# flute.net
KiCad netlist of a schematic drawn in EAGLE
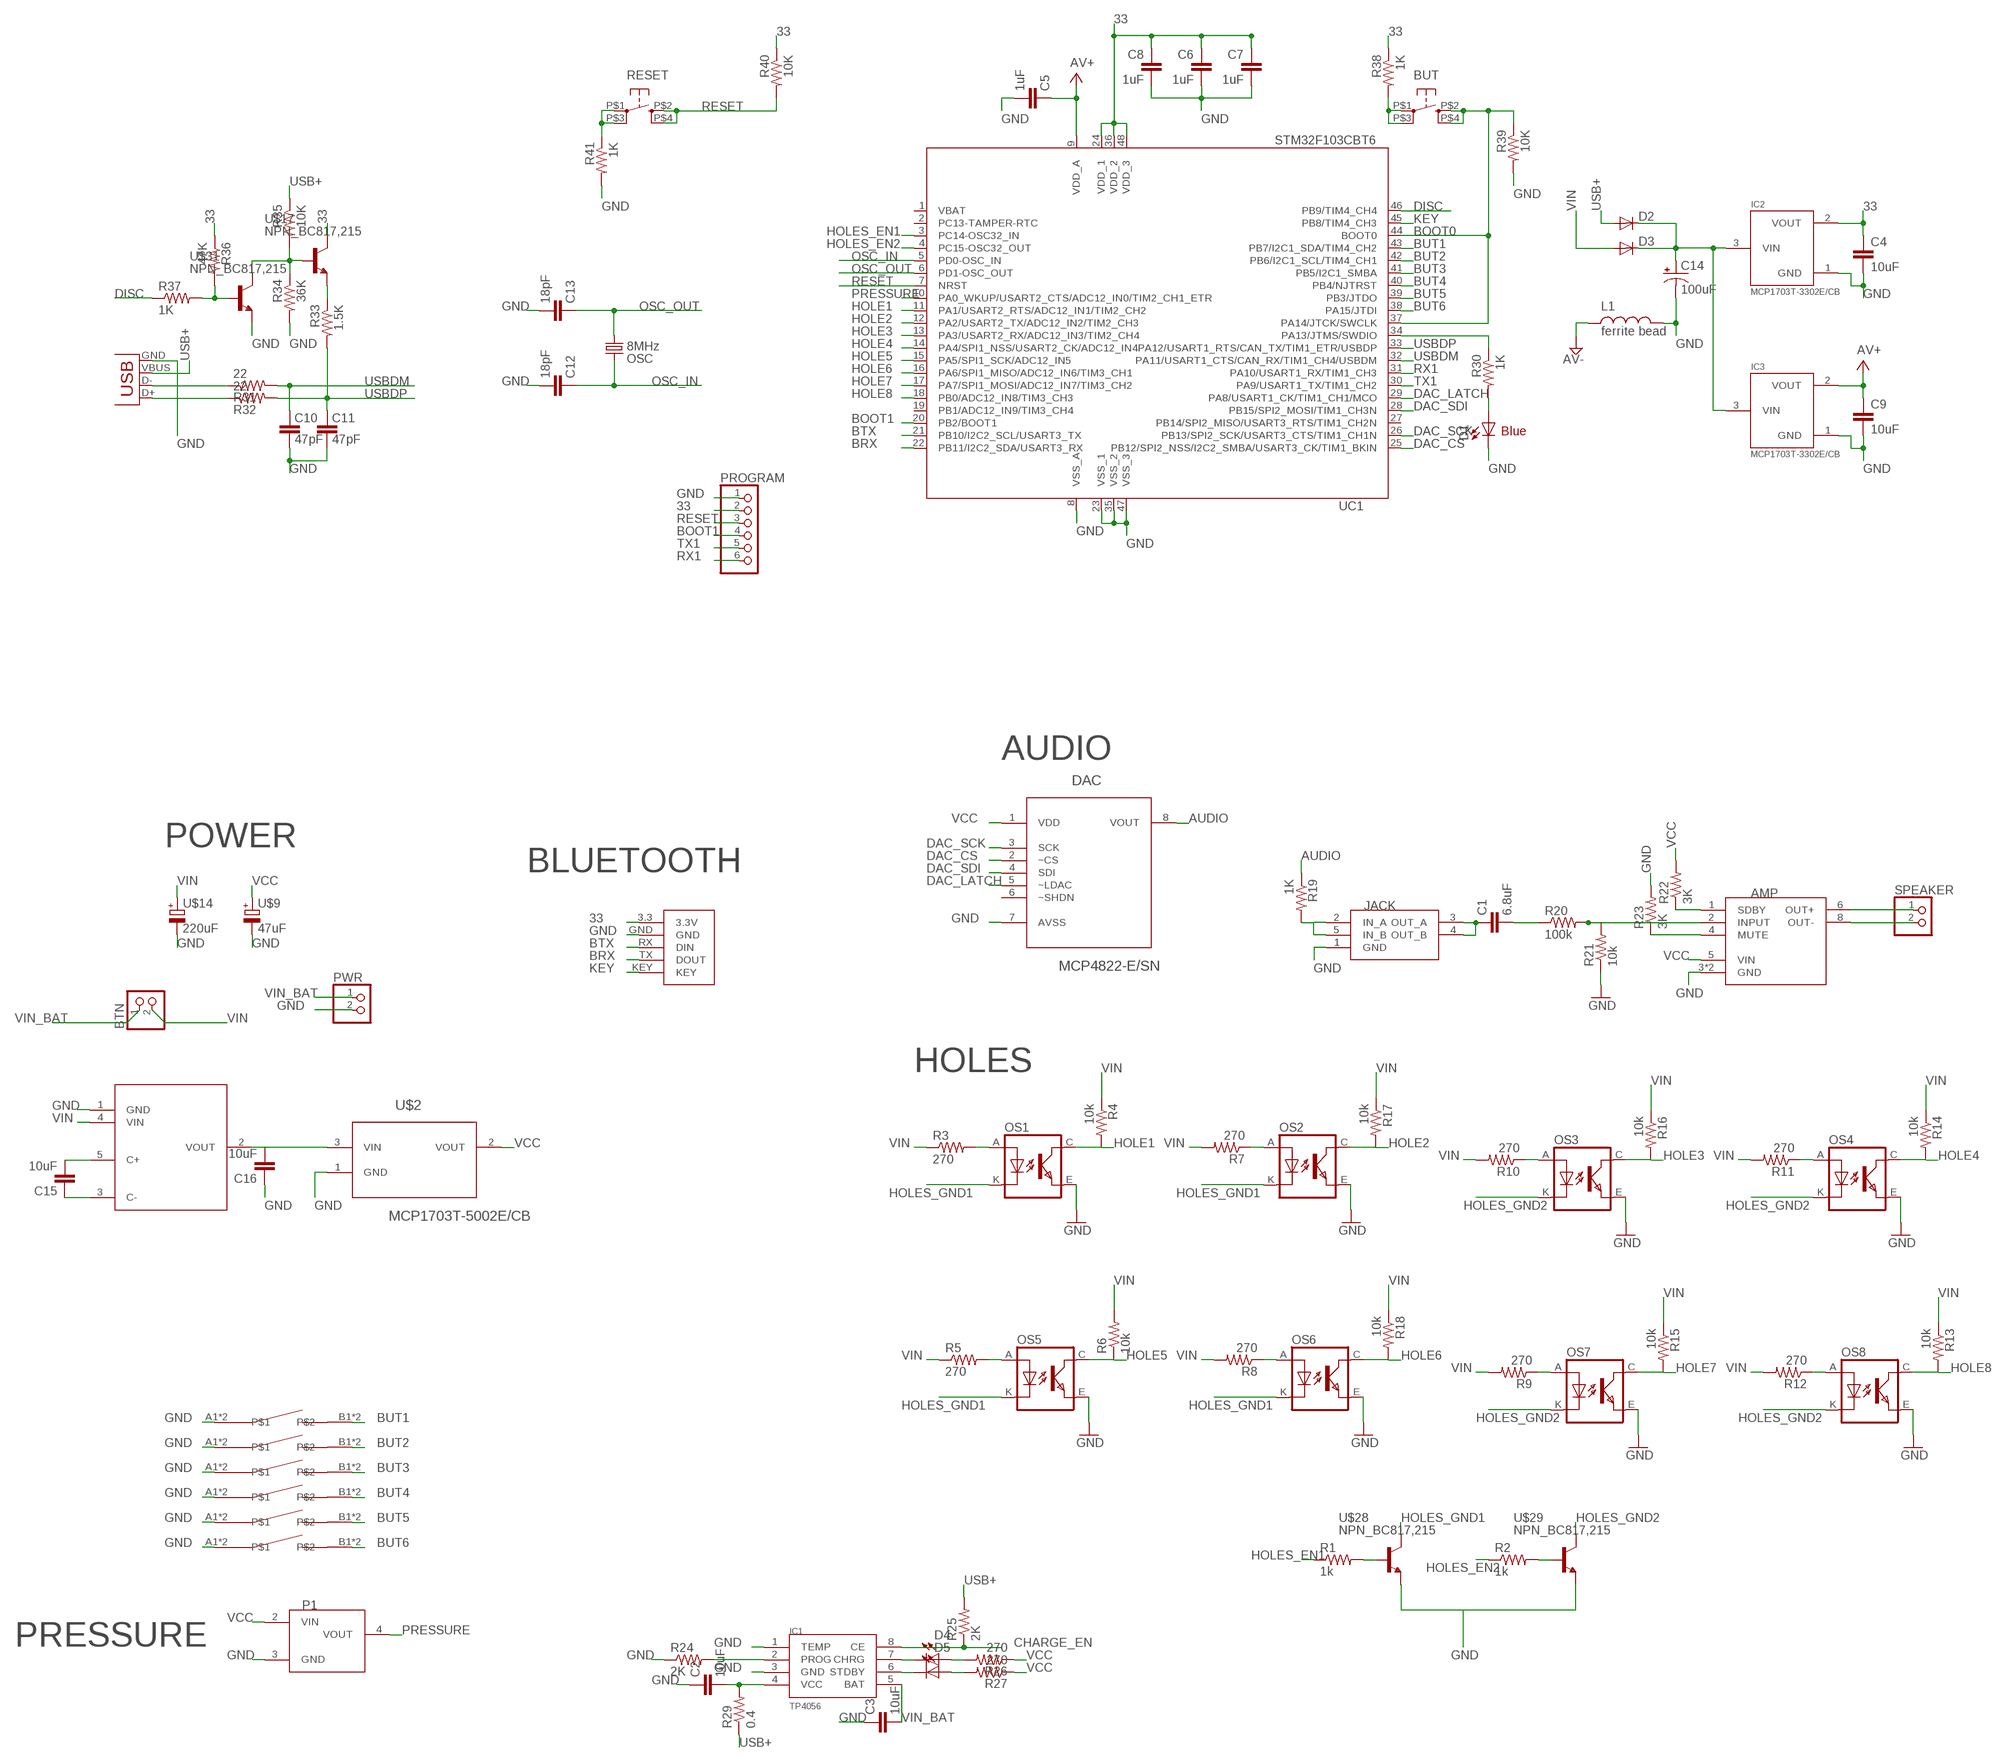
[diagram p0: schematic, sheet 1]

(export (version "E")
  (design (tool "Eeschema 10.0.6"))
  (components
    (comp (ref "AMP")
      (value "AN7511DIP8")
      (footprint "eagle-import:DIL08")
      (libsource (lib "eagle-import") (part "AN7511DIP8"))
    )
    (comp (ref "BTN")
      (value "CONNEC_1X02BASIC")
      (footprint "eagle-import:CONNEC_1X02")
      (libsource (lib "eagle-import") (part "CONNEC_1X02BASIC"))
    )
    (comp (ref "BUT")
      (value "KMR211GLFS")
      (footprint "eagle-import:PUSHBUTTON-KMR241GLFS")
      (libsource (lib "eagle-import") (part "BUTTON-KMR241GLFS"))
    )
    (comp (ref "C1")
      (value "6.8uF")
      (footprint "eagle-import:0805")
      (libsource (lib "eagle-import") (part "SparkFun-Passives_CAP0805"))
    )
    (comp (ref "C2")
      (value "10uF")
      (footprint "eagle-import:0805")
      (libsource (lib "eagle-import") (part "SparkFun-Passives_CAP0805"))
    )
    (comp (ref "C3")
      (value "10uF")
      (footprint "eagle-import:0805")
      (libsource (lib "eagle-import") (part "SparkFun-Passives_CAP0805"))
    )
    (comp (ref "C4")
      (value "10uF")
      (footprint "eagle-import:0805")
      (libsource (lib "eagle-import") (part "SparkFun2_CAP0805"))
    )
    (comp (ref "C5")
      (value "1uF")
      (footprint "eagle-import:C0402")
      (libsource (lib "eagle-import") (part "CAP0402"))
    )
    (comp (ref "C6")
      (value "1uF")
      (footprint "eagle-import:C0402")
      (libsource (lib "eagle-import") (part "CAP0402"))
    )
    (comp (ref "C7")
      (value "1uF")
      (footprint "eagle-import:C0402")
      (libsource (lib "eagle-import") (part "CAP0402"))
    )
    (comp (ref "C8")
      (value "1uF")
      (footprint "eagle-import:C0402")
      (libsource (lib "eagle-import") (part "CAP0402"))
    )
    (comp (ref "C9")
      (value "10uF")
      (footprint "eagle-import:0805")
      (libsource (lib "eagle-import") (part "SparkFun2_CAP0805"))
    )
    (comp (ref "C10")
      (value "47pF")
      (footprint "eagle-import:C0402")
      (libsource (lib "eagle-import") (part "CAP0402"))
    )
    (comp (ref "C11")
      (value "47pF")
      (footprint "eagle-import:C0402")
      (libsource (lib "eagle-import") (part "CAP0402"))
    )
    (comp (ref "C12")
      (value "18pF")
      (footprint "eagle-import:C0402")
      (libsource (lib "eagle-import") (part "CAP0402"))
    )
    (comp (ref "C13")
      (value "18pF")
      (footprint "eagle-import:C0402")
      (libsource (lib "eagle-import") (part "CAP0402"))
    )
    (comp (ref "C14")
      (value "100uF")
      (footprint "eagle-import:EIA3216")
      (libsource (lib "eagle-import") (part "CAP_POL1206"))
    )
    (comp (ref "C15")
      (value "10uF")
      (footprint "eagle-import:0805")
      (libsource (lib "eagle-import") (part "SparkFun-Passives_CAP0805"))
    )
    (comp (ref "C16")
      (value "10uF")
      (footprint "eagle-import:0805")
      (libsource (lib "eagle-import") (part "SparkFun-Passives_CAP0805"))
    )
    (comp (ref "D1")
      (value "Blue")
      (footprint "eagle-import:LED-1206")
      (libsource (lib "eagle-import") (part "LED1206"))
    )
    (comp (ref "D2")
      (value "DIODESOD")
      (footprint "eagle-import:SOD-323")
      (libsource (lib "eagle-import") (part "DIODESOD"))
    )
    (comp (ref "D3")
      (value "DIODESOD")
      (footprint "eagle-import:SOD-323")
      (libsource (lib "eagle-import") (part "DIODESOD"))
    )
    (comp (ref "D4")
      (value "Red")
      (footprint "eagle-import:LED-1206")
      (libsource (lib "eagle-import") (part "LED1206"))
    )
    (comp (ref "D5")
      (value "Green")
      (footprint "eagle-import:LED-1206")
      (libsource (lib "eagle-import") (part "LED1206"))
    )
    (comp (ref "DAC")
      (value "MCP4822-E/SN")
      (footprint "eagle-import:SOIC8-N_MC")
      (libsource (lib "eagle-import") (part "MCP4822-E/SN"))
    )
    (comp (ref "IC1")
      (value "TP4056")
      (footprint "eagle-import:SOP-8")
      (libsource (lib "eagle-import") (part "TP4056"))
    )
    (comp (ref "IC2")
      (value "MCP1703T-3302E/CB")
      (footprint "eagle-import:SOT23")
      (libsource (lib "eagle-import") (part "MCP1700T"))
    )
    (comp (ref "IC3")
      (value "MCP1703T-3302E/CB")
      (footprint "eagle-import:SOT23")
      (libsource (lib "eagle-import") (part "MCP1700T"))
    )
    (comp (ref "JACK")
      (value "JACK")
      (footprint "eagle-import:3F07")
      (libsource (lib "eagle-import") (part "JACK"))
    )
    (comp (ref "L1")
      (value "ferrite bead")
      (footprint "eagle-import:0603")
      (libsource (lib "eagle-import") (part "INDUCTOR0603"))
    )
    (comp (ref "OS1")
      (value "TCRT5000")
      (footprint "eagle-import:TCRT5000")
      (libsource (lib "eagle-import") (part "TCRT5000"))
    )
    (comp (ref "OS2")
      (value "TCRT5000")
      (footprint "eagle-import:TCRT5000")
      (libsource (lib "eagle-import") (part "TCRT5000"))
    )
    (comp (ref "OS3")
      (value "TCRT5000")
      (footprint "eagle-import:TCRT5000")
      (libsource (lib "eagle-import") (part "TCRT5000"))
    )
    (comp (ref "OS4")
      (value "TCRT5000")
      (footprint "eagle-import:TCRT5000")
      (libsource (lib "eagle-import") (part "TCRT5000"))
    )
    (comp (ref "OS5")
      (value "TCRT5000")
      (footprint "eagle-import:TCRT5000")
      (libsource (lib "eagle-import") (part "TCRT5000"))
    )
    (comp (ref "OS6")
      (value "TCRT5000")
      (footprint "eagle-import:TCRT5000")
      (libsource (lib "eagle-import") (part "TCRT5000"))
    )
    (comp (ref "OS7")
      (value "TCRT5000")
      (footprint "eagle-import:TCRT5000")
      (libsource (lib "eagle-import") (part "TCRT5000"))
    )
    (comp (ref "OS8")
      (value "TCRT5000")
      (footprint "eagle-import:TCRT5000")
      (libsource (lib "eagle-import") (part "TCRT5000"))
    )
    (comp (ref "OSC")
      (value "8MHz")
      (footprint "eagle-import:CRYSTAL-SMD-5X3")
      (libsource (lib "eagle-import") (part "CRYSTAL5X3"))
    )
    (comp (ref "P1")
      (value "PRESSURE_SENSOR")
      (footprint "eagle-import:MPXV5050GP")
      (libsource (lib "eagle-import") (part "PRESSURE_SENSOR"))
    )
    (comp (ref "PROGRAM")
      (value "CONNEC_1X066PADS")
      (footprint "eagle-import:6PADS")
      (libsource (lib "eagle-import") (part "CONNEC_1X066PADS"))
    )
    (comp (ref "PWR")
      (value "CONNEC_1X02BASIC")
      (footprint "eagle-import:CONNEC_1X02")
      (libsource (lib "eagle-import") (part "CONNEC_1X02BASIC"))
    )
    (comp (ref "R1")
      (value "1k")
      (footprint "eagle-import:0805")
      (libsource (lib "eagle-import") (part "RESISTOR0805-RES"))
    )
    (comp (ref "R2")
      (value "1k")
      (footprint "eagle-import:0805")
      (libsource (lib "eagle-import") (part "RESISTOR0805-RES"))
    )
    (comp (ref "R3")
      (value "270")
      (footprint "eagle-import:0805")
      (libsource (lib "eagle-import") (part "RESISTOR0805-RES"))
    )
    (comp (ref "R4")
      (value "10k")
      (footprint "eagle-import:0805")
      (libsource (lib "eagle-import") (part "RESISTOR0805-RES"))
    )
    (comp (ref "R5")
      (value "270")
      (footprint "eagle-import:0805")
      (libsource (lib "eagle-import") (part "RESISTOR0805-RES"))
    )
    (comp (ref "R6")
      (value "10k")
      (footprint "eagle-import:0805")
      (libsource (lib "eagle-import") (part "RESISTOR0805-RES"))
    )
    (comp (ref "R7")
      (value "270")
      (footprint "eagle-import:0805")
      (libsource (lib "eagle-import") (part "RESISTOR0805-RES"))
    )
    (comp (ref "R8")
      (value "270")
      (footprint "eagle-import:0805")
      (libsource (lib "eagle-import") (part "RESISTOR0805-RES"))
    )
    (comp (ref "R9")
      (value "270")
      (footprint "eagle-import:0805")
      (libsource (lib "eagle-import") (part "RESISTOR0805-RES"))
    )
    (comp (ref "R10")
      (value "270")
      (footprint "eagle-import:0805")
      (libsource (lib "eagle-import") (part "RESISTOR0805-RES"))
    )
    (comp (ref "R11")
      (value "270")
      (footprint "eagle-import:0805")
      (libsource (lib "eagle-import") (part "RESISTOR0805-RES"))
    )
    (comp (ref "R12")
      (value "270")
      (footprint "eagle-import:0805")
      (libsource (lib "eagle-import") (part "RESISTOR0805-RES"))
    )
    (comp (ref "R13")
      (value "10k")
      (footprint "eagle-import:0805")
      (libsource (lib "eagle-import") (part "RESISTOR0805-RES"))
    )
    (comp (ref "R14")
      (value "10k")
      (footprint "eagle-import:0805")
      (libsource (lib "eagle-import") (part "RESISTOR0805-RES"))
    )
    (comp (ref "R15")
      (value "10k")
      (footprint "eagle-import:0805")
      (libsource (lib "eagle-import") (part "RESISTOR0805-RES"))
    )
    (comp (ref "R16")
      (value "10k")
      (footprint "eagle-import:0805")
      (libsource (lib "eagle-import") (part "RESISTOR0805-RES"))
    )
    (comp (ref "R17")
      (value "10k")
      (footprint "eagle-import:0805")
      (libsource (lib "eagle-import") (part "RESISTOR0805-RES"))
    )
    (comp (ref "R18")
      (value "10k")
      (footprint "eagle-import:0805")
      (libsource (lib "eagle-import") (part "RESISTOR0805-RES"))
    )
    (comp (ref "R19")
      (value "1K")
      (footprint "eagle-import:0805")
      (libsource (lib "eagle-import") (part "RESISTOR0805-RES"))
    )
    (comp (ref "R20")
      (value "100k")
      (footprint "eagle-import:0805")
      (libsource (lib "eagle-import") (part "RESISTOR0805-RES"))
    )
    (comp (ref "R21")
      (value "10k")
      (footprint "eagle-import:0805")
      (libsource (lib "eagle-import") (part "RESISTOR0805-RES"))
    )
    (comp (ref "R22")
      (value "3K")
      (footprint "eagle-import:0805")
      (libsource (lib "eagle-import") (part "RESISTOR0805-RES"))
    )
    (comp (ref "R23")
      (value "3K")
      (footprint "eagle-import:0805")
      (libsource (lib "eagle-import") (part "RESISTOR0805-RES"))
    )
    (comp (ref "R24")
      (value "2K")
      (footprint "eagle-import:0805")
      (libsource (lib "eagle-import") (part "RESISTOR0805-RES"))
    )
    (comp (ref "R25")
      (value "2K")
      (footprint "eagle-import:0805")
      (libsource (lib "eagle-import") (part "RESISTOR0805-RES"))
    )
    (comp (ref "R26")
      (value "270")
      (footprint "eagle-import:0805")
      (libsource (lib "eagle-import") (part "RESISTOR0805-RES"))
    )
    (comp (ref "R27")
      (value "270")
      (footprint "eagle-import:0805")
      (libsource (lib "eagle-import") (part "RESISTOR0805-RES"))
    )
    (comp (ref "R29")
      (value "0.4")
      (footprint "eagle-import:0805")
      (libsource (lib "eagle-import") (part "RESISTOR0805-RES"))
    )
    (comp (ref "R30")
      (value "1K")
      (footprint "eagle-import:0805")
      (libsource (lib "eagle-import") (part "RESISTOR0805-RES"))
    )
    (comp (ref "R31")
      (value "22")
      (footprint "eagle-import:0805")
      (libsource (lib "eagle-import") (part "RESISTOR0805-RES"))
    )
    (comp (ref "R32")
      (value "22")
      (footprint "eagle-import:0805")
      (libsource (lib "eagle-import") (part "RESISTOR0805-RES"))
    )
    (comp (ref "R33")
      (value "1.5K")
      (footprint "eagle-import:0805")
      (libsource (lib "eagle-import") (part "RESISTOR0805-RES"))
    )
    (comp (ref "R34")
      (value "36K")
      (footprint "eagle-import:0805")
      (libsource (lib "eagle-import") (part "RESISTOR0805-RES"))
    )
    (comp (ref "R35")
      (value "10K")
      (footprint "eagle-import:0805")
      (libsource (lib "eagle-import") (part "RESISTOR0805-RES"))
    )
    (comp (ref "R36")
      (value "47K")
      (footprint "eagle-import:0805")
      (libsource (lib "eagle-import") (part "RESISTOR0805-RES"))
    )
    (comp (ref "R37")
      (value "1K")
      (footprint "eagle-import:0805")
      (libsource (lib "eagle-import") (part "RESISTOR0805-RES"))
    )
    (comp (ref "R38")
      (value "1K")
      (footprint "eagle-import:0805")
      (libsource (lib "eagle-import") (part "RESISTOR0805-RES"))
    )
    (comp (ref "R39")
      (value "10K")
      (footprint "eagle-import:0805")
      (libsource (lib "eagle-import") (part "RESISTOR0805-RES"))
    )
    (comp (ref "R40")
      (value "10K")
      (footprint "eagle-import:0805")
      (libsource (lib "eagle-import") (part "RESISTOR0805-RES"))
    )
    (comp (ref "R41")
      (value "1K")
      (footprint "eagle-import:0805")
      (libsource (lib "eagle-import") (part "RESISTOR0805-RES"))
    )
    (comp (ref "RESET")
      (value "KMR211GLFS")
      (footprint "eagle-import:PUSHBUTTON-KMR241GLFS")
      (libsource (lib "eagle-import") (part "BUTTON-KMR241GLFS"))
    )
    (comp (ref "SPEAKER")
      (value "CONNEC_1X02BASIC")
      (footprint "eagle-import:CONNEC_1X02")
      (libsource (lib "eagle-import") (part "CONNEC_1X02BASIC"))
    )
    (comp (ref "U$1")
      (value "MAX1683")
      (footprint "eagle-import:SOT23-5")
      (libsource (lib "eagle-import") (part "MAX1683"))
    )
    (comp (ref "U$2")
      (value "MCP1703T-5002E/CB")
      (footprint "eagle-import:SOT95P300X145-3N")
      (libsource (lib "eagle-import") (part "MCP1703T-5002E/CB"))
    )
    (comp (ref "U$9")
      (value "47uF")
      (footprint "eagle-import:PANASONIC_D")
      (libsource (lib "eagle-import") (part "CPOL_EUPANASONIC_D"))
    )
    (comp (ref "U$14")
      (value "220uF")
      (footprint "eagle-import:PANASONIC_D8")
      (libsource (lib "eagle-import") (part "CPOL_EUPANASONIC_D8"))
    )
    (comp (ref "U$17")
      (value "NPN_BC817,215")
      (footprint "eagle-import:SOT-23")
      (libsource (lib "eagle-import") (part "NPN_BC817,215"))
    )
    (comp (ref "U$18")
      (value "SWITCH6X6X10")
      (footprint "eagle-import:SWITCH_6X6X10")
      (libsource (lib "eagle-import") (part "SWITCH6X6X10"))
    )
    (comp (ref "U$19")
      (value "SWITCH6X6X10")
      (footprint "eagle-import:SWITCH_6X6X10")
      (libsource (lib "eagle-import") (part "SWITCH6X6X10"))
    )
    (comp (ref "U$20")
      (value "SWITCH6X6X10")
      (footprint "eagle-import:SWITCH_6X6X10")
      (libsource (lib "eagle-import") (part "SWITCH6X6X10"))
    )
    (comp (ref "U$21")
      (value "SWITCH6X6X10")
      (footprint "eagle-import:SWITCH_6X6X10")
      (libsource (lib "eagle-import") (part "SWITCH6X6X10"))
    )
    (comp (ref "U$22")
      (value "SWITCH6X6X10")
      (footprint "eagle-import:SWITCH_6X6X10")
      (libsource (lib "eagle-import") (part "SWITCH6X6X10"))
    )
    (comp (ref "U$23")
      (value "SWITCH6X6X10")
      (footprint "eagle-import:SWITCH_6X6X10")
      (libsource (lib "eagle-import") (part "SWITCH6X6X10"))
    )
    (comp (ref "U$24")
      (value "HC05")
      (footprint "eagle-import:HC-05")
      (libsource (lib "eagle-import") (part "HC05"))
    )
    (comp (ref "U$28")
      (value "NPN_BC817,215")
      (footprint "eagle-import:SOT-23")
      (libsource (lib "eagle-import") (part "NPN_BC817,215"))
    )
    (comp (ref "U$29")
      (value "NPN_BC817,215")
      (footprint "eagle-import:SOT-23")
      (libsource (lib "eagle-import") (part "NPN_BC817,215"))
    )
    (comp (ref "U$31")
      (value "NPN_BC817,215")
      (footprint "eagle-import:SOT-23")
      (libsource (lib "eagle-import") (part "NPN_BC817,215"))
    )
    (comp (ref "UC1")
      (value "STM32F103CBT6")
      (footprint "eagle-import:LQFP48")
      (libsource (lib "eagle-import") (part "STM32F103CB"))
    )
    (comp (ref "X1")
      (value "USB-MINIB")
      (footprint "eagle-import:USB-MINIB")
      (libsource (lib "eagle-import") (part "USBSMD"))
    )
  )
  (nets
    (net (code "1") (name "/33") (class "Default")
      (node (ref "C4") (pin "1") (pinfunction "1_1") (pintype "passive"))
      (node (ref "C6") (pin "1") (pinfunction "1_1") (pintype "passive"))
      (node (ref "C7") (pin "1") (pinfunction "1_1") (pintype "passive"))
      (node (ref "C8") (pin "1") (pinfunction "1_1") (pintype "passive"))
      (node (ref "IC2") (pin "2") (pinfunction "VOUT_2") (pintype "bidirectional"))
      (node (ref "PROGRAM") (pin "2") (pinfunction "2_2") (pintype "passive"))
      (node (ref "R36") (pin "1") (pinfunction "1_1") (pintype "passive"))
      (node (ref "R38") (pin "1") (pinfunction "1_1") (pintype "passive"))
      (node (ref "R40") (pin "1") (pinfunction "1_1") (pintype "passive"))
      (node (ref "U$17") (pin "3") (pinfunction "C_3") (pintype "passive"))
      (node (ref "U$24") (pin "3.3") (pinfunction "3.3V_3.3") (pintype "bidirectional"))
      (node (ref "UC1") (pin "24") (pinfunction "VDD_1_24") (pintype "power_in"))
      (node (ref "UC1") (pin "36") (pinfunction "VDD_2_36") (pintype "power_in"))
      (node (ref "UC1") (pin "48") (pinfunction "VDD_3_48") (pintype "power_in"))
    )
    (net (code "2") (name "/AUDIO") (class "Default")
      (node (ref "DAC") (pin "8") (pinfunction "VOUT_8") (pintype "output"))
      (node (ref "R19") (pin "1") (pinfunction "1_1") (pintype "passive"))
    )
    (net (code "3") (name "/BOOT1") (class "Default")
      (node (ref "PROGRAM") (pin "4") (pinfunction "4_4") (pintype "passive"))
      (node (ref "UC1") (pin "20") (pinfunction "PB2/BOOT1_20") (pintype "bidirectional"))
    )
    (net (code "4") (name "/BRX") (class "Default")
      (node (ref "U$24") (pin "TX") (pinfunction "DOUT_TX") (pintype "bidirectional"))
      (node (ref "UC1") (pin "22") (pinfunction "PB11/I2C2_SDA/USART3_RX_22") (pintype "input"))
    )
    (net (code "5") (name "/BTX") (class "Default")
      (node (ref "U$24") (pin "RX") (pinfunction "DIN_RX") (pintype "bidirectional"))
      (node (ref "UC1") (pin "21") (pinfunction "PB10/I2C2_SCL/USART3_TX_21") (pintype "input"))
    )
    (net (code "6") (name "/BUT1") (class "Default")
      (node (ref "U$18") (pin "B1") (pinfunction "P$2_B1") (pintype "bidirectional"))
      (node (ref "U$18") (pin "B2") (pinfunction "P$2_B2") (pintype "bidirectional"))
      (node (ref "UC1") (pin "43") (pinfunction "PB7/I2C1_SDA/TIM4_CH2_43") (pintype "bidirectional"))
    )
    (net (code "7") (name "/BUT2") (class "Default")
      (node (ref "U$19") (pin "B1") (pinfunction "P$2_B1") (pintype "bidirectional"))
      (node (ref "U$19") (pin "B2") (pinfunction "P$2_B2") (pintype "bidirectional"))
      (node (ref "UC1") (pin "42") (pinfunction "PB6/I2C1_SCL/TIM4_CH1_42") (pintype "input"))
    )
    (net (code "8") (name "/BUT3") (class "Default")
      (node (ref "U$20") (pin "B1") (pinfunction "P$2_B1") (pintype "bidirectional"))
      (node (ref "U$20") (pin "B2") (pinfunction "P$2_B2") (pintype "bidirectional"))
      (node (ref "UC1") (pin "41") (pinfunction "PB5/I2C1_SMBA_41") (pintype "input"))
    )
    (net (code "9") (name "/BUT4") (class "Default")
      (node (ref "U$21") (pin "B1") (pinfunction "P$2_B1") (pintype "bidirectional"))
      (node (ref "U$21") (pin "B2") (pinfunction "P$2_B2") (pintype "bidirectional"))
      (node (ref "UC1") (pin "40") (pinfunction "PB4/NJTRST_40") (pintype "bidirectional"))
    )
    (net (code "10") (name "/BUT5") (class "Default")
      (node (ref "U$22") (pin "B1") (pinfunction "P$2_B1") (pintype "bidirectional"))
      (node (ref "U$22") (pin "B2") (pinfunction "P$2_B2") (pintype "bidirectional"))
      (node (ref "UC1") (pin "39") (pinfunction "PB3/JTDO_39") (pintype "bidirectional"))
    )
    (net (code "11") (name "/BUT6") (class "Default")
      (node (ref "U$23") (pin "B1") (pinfunction "P$2_B1") (pintype "bidirectional"))
      (node (ref "U$23") (pin "B2") (pinfunction "P$2_B2") (pintype "bidirectional"))
      (node (ref "UC1") (pin "38") (pinfunction "PA15/JTDI_38") (pintype "bidirectional"))
    )
    (net (code "12") (name "/CHARGE_EN") (class "Default")
      (node (ref "IC1") (pin "8") (pinfunction "CE_8") (pintype "bidirectional"))
      (node (ref "R25") (pin "1") (pinfunction "1_1") (pintype "passive"))
    )
    (net (code "13") (name "/DAC_CS") (class "Default")
      (node (ref "DAC") (pin "2") (pinfunction "~{CS}_2") (pintype "input"))
      (node (ref "UC1") (pin "25") (pinfunction "PB12/SPI2_NSS/I2C2_SMBA/USART3_CK/TIM1_BKIN_25") (pintype "input"))
    )
    (net (code "14") (name "/DAC_LATCH") (class "Default")
      (node (ref "DAC") (pin "5") (pinfunction "~{LDAC}_5") (pintype "input"))
      (node (ref "UC1") (pin "29") (pinfunction "PA8/USART1_CK/TIM1_CH1/MCO_29") (pintype "bidirectional"))
    )
    (net (code "15") (name "/DAC_SCK") (class "Default")
      (node (ref "DAC") (pin "3") (pinfunction "SCK_3") (pintype "input"))
      (node (ref "UC1") (pin "26") (pinfunction "PB13/SPI2_SCK/USART3_CTS/TIM1_CH1N_26") (pintype "input"))
    )
    (net (code "16") (name "/DAC_SDI") (class "Default")
      (node (ref "DAC") (pin "4") (pinfunction "SDI_4") (pintype "input"))
      (node (ref "UC1") (pin "28") (pinfunction "PB15/SPI2_MOSI/TIM1_CH3N_28") (pintype "input"))
    )
    (net (code "17") (name "/DISC") (class "Default")
      (node (ref "R37") (pin "1") (pinfunction "1_1") (pintype "passive"))
      (node (ref "UC1") (pin "46") (pinfunction "PB9/TIM4_CH4_46") (pintype "input"))
    )
    (net (code "18") (name "/HOLE1") (class "Default")
      (node (ref "OS1") (pin "C") (pinfunction "COLLECTOR_C") (pintype "passive"))
      (node (ref "R4") (pin "2") (pinfunction "2_2") (pintype "passive"))
      (node (ref "UC1") (pin "11") (pinfunction "PA1/USART2_RTS/ADC12_IN1/TIM2_CH2_11") (pintype "bidirectional"))
    )
    (net (code "19") (name "/HOLE2") (class "Default")
      (node (ref "OS2") (pin "C") (pinfunction "COLLECTOR_C") (pintype "passive"))
      (node (ref "R17") (pin "2") (pinfunction "2_2") (pintype "passive"))
      (node (ref "UC1") (pin "12") (pinfunction "PA2/USART2_TX/ADC12_IN2/TIM2_CH3_12") (pintype "bidirectional"))
    )
    (net (code "20") (name "/HOLE3") (class "Default")
      (node (ref "OS3") (pin "C") (pinfunction "COLLECTOR_C") (pintype "passive"))
      (node (ref "R16") (pin "2") (pinfunction "2_2") (pintype "passive"))
      (node (ref "UC1") (pin "13") (pinfunction "PA3/USART2_RX/ADC12_IN3/TIM2_CH4_13") (pintype "bidirectional"))
    )
    (net (code "21") (name "/HOLE4") (class "Default")
      (node (ref "OS4") (pin "C") (pinfunction "COLLECTOR_C") (pintype "passive"))
      (node (ref "R14") (pin "2") (pinfunction "2_2") (pintype "passive"))
      (node (ref "UC1") (pin "14") (pinfunction "PA4/SPI1_NSS/USART2_CK/ADC12_IN4_14") (pintype "bidirectional"))
    )
    (net (code "22") (name "/HOLE5") (class "Default")
      (node (ref "OS5") (pin "C") (pinfunction "COLLECTOR_C") (pintype "passive"))
      (node (ref "R6") (pin "1") (pinfunction "1_1") (pintype "passive"))
      (node (ref "UC1") (pin "15") (pinfunction "PA5/SPI1_SCK/ADC12_IN5_15") (pintype "bidirectional"))
    )
    (net (code "23") (name "/HOLE6") (class "Default")
      (node (ref "OS6") (pin "C") (pinfunction "COLLECTOR_C") (pintype "passive"))
      (node (ref "R18") (pin "2") (pinfunction "2_2") (pintype "passive"))
      (node (ref "UC1") (pin "16") (pinfunction "PA6/SPI1_MISO/ADC12_IN6/TIM3_CH1_16") (pintype "bidirectional"))
    )
    (net (code "24") (name "/HOLE7") (class "Default")
      (node (ref "OS7") (pin "C") (pinfunction "COLLECTOR_C") (pintype "passive"))
      (node (ref "R15") (pin "2") (pinfunction "2_2") (pintype "passive"))
      (node (ref "UC1") (pin "17") (pinfunction "PA7/SPI1_MOSI/ADC12_IN7/TIM3_CH2_17") (pintype "bidirectional"))
    )
    (net (code "25") (name "/HOLE8") (class "Default")
      (node (ref "OS8") (pin "C") (pinfunction "COLLECTOR_C") (pintype "passive"))
      (node (ref "R13") (pin "2") (pinfunction "2_2") (pintype "passive"))
      (node (ref "UC1") (pin "18") (pinfunction "PB0/ADC12_IN8/TIM3_CH3_18") (pintype "bidirectional"))
    )
    (net (code "26") (name "/HOLES_EN1") (class "Default")
      (node (ref "R1") (pin "1") (pinfunction "1_1") (pintype "passive"))
      (node (ref "UC1") (pin "3") (pinfunction "PC14-OSC32_IN_3") (pintype "input"))
    )
    (net (code "27") (name "/HOLES_EN2") (class "Default")
      (node (ref "R2") (pin "1") (pinfunction "1_1") (pintype "passive"))
      (node (ref "UC1") (pin "4") (pinfunction "PC15-OSC32_OUT_4") (pintype "input"))
    )
    (net (code "28") (name "/HOLES_GND1") (class "Default")
      (node (ref "OS1") (pin "K") (pinfunction "CATHODE_K") (pintype "passive"))
      (node (ref "OS2") (pin "K") (pinfunction "CATHODE_K") (pintype "passive"))
      (node (ref "OS5") (pin "K") (pinfunction "CATHODE_K") (pintype "passive"))
      (node (ref "OS6") (pin "K") (pinfunction "CATHODE_K") (pintype "passive"))
      (node (ref "U$28") (pin "3") (pinfunction "C_3") (pintype "passive"))
    )
    (net (code "29") (name "/HOLES_GND2") (class "Default")
      (node (ref "OS3") (pin "K") (pinfunction "CATHODE_K") (pintype "passive"))
      (node (ref "OS4") (pin "K") (pinfunction "CATHODE_K") (pintype "passive"))
      (node (ref "OS7") (pin "K") (pinfunction "CATHODE_K") (pintype "passive"))
      (node (ref "OS8") (pin "K") (pinfunction "CATHODE_K") (pintype "passive"))
      (node (ref "U$29") (pin "3") (pinfunction "C_3") (pintype "passive"))
    )
    (net (code "30") (name "/KEY") (class "Default")
      (node (ref "U$24") (pin "KEY") (pinfunction "KEY_KEY") (pintype "bidirectional"))
      (node (ref "UC1") (pin "45") (pinfunction "PB8/TIM4_CH3_45") (pintype "bidirectional"))
    )
    (net (code "31") (name "/OSC_IN") (class "Default")
      (node (ref "C12") (pin "1") (pinfunction "1_1") (pintype "passive"))
      (node (ref "OSC") (pin "3") (pinfunction "2_3") (pintype "passive"))
      (node (ref "UC1") (pin "5") (pinfunction "PD0-OSC_IN_5") (pintype "input"))
    )
    (net (code "32") (name "/OSC_OUT") (class "Default")
      (node (ref "C13") (pin "1") (pinfunction "1_1") (pintype "passive"))
      (node (ref "OSC") (pin "1") (pinfunction "1_1") (pintype "passive"))
      (node (ref "UC1") (pin "6") (pinfunction "PD1-OSC_OUT_6") (pintype "input"))
    )
    (net (code "33") (name "/PRESSURE") (class "Default")
      (node (ref "P1") (pin "4") (pinfunction "VOUT_4") (pintype "bidirectional"))
      (node (ref "UC1") (pin "10") (pinfunction "PA0_WKUP/USART2_CTS/ADC12_IN0/TIM2_CH1_ETR_10") (pintype "bidirectional"))
    )
    (net (code "34") (name "/RESET") (class "Default")
      (node (ref "PROGRAM") (pin "3") (pinfunction "3_3") (pintype "passive"))
      (node (ref "R40") (pin "2") (pinfunction "2_2") (pintype "passive"))
      (node (ref "RESET") (pin "P$2") (pinfunction "2_P$2") (pintype "passive"))
      (node (ref "RESET") (pin "P$4") (pinfunction "4_P$4") (pintype "passive"))
      (node (ref "UC1") (pin "7") (pinfunction "NRST_7") (pintype "input"))
    )
    (net (code "35") (name "/RX1") (class "Default")
      (node (ref "PROGRAM") (pin "6") (pinfunction "6_6") (pintype "passive"))
      (node (ref "UC1") (pin "31") (pinfunction "PA10/USART1_RX/TIM1_CH3_31") (pintype "bidirectional"))
    )
    (net (code "36") (name "/TX1") (class "Default")
      (node (ref "PROGRAM") (pin "5") (pinfunction "5_5") (pintype "passive"))
      (node (ref "UC1") (pin "30") (pinfunction "PA9/USART1_TX/TIM1_CH2_30") (pintype "input"))
    )
    (net (code "37") (name "/USB+") (class "Default")
      (node (ref "D2") (pin "2") (pinfunction "A_2") (pintype "passive"))
      (node (ref "R25") (pin "2") (pinfunction "2_2") (pintype "passive"))
      (node (ref "R29") (pin "1") (pinfunction "1_1") (pintype "passive"))
      (node (ref "R35") (pin "1") (pinfunction "1_1") (pintype "passive"))
      (node (ref "X1") (pin "VBUS") (pinfunction "VBUS_VBUS") (pintype "bidirectional"))
    )
    (net (code "38") (name "/USBDM") (class "Default")
      (node (ref "C10") (pin "2") (pinfunction "2_2") (pintype "passive"))
      (node (ref "R31") (pin "2") (pinfunction "2_2") (pintype "passive"))
      (node (ref "UC1") (pin "32") (pinfunction "PA11/USART1_CTS/CAN_RX/TIM1_CH4/USBDM_32") (pintype "bidirectional"))
    )
    (net (code "39") (name "/USBDP") (class "Default")
      (node (ref "C11") (pin "2") (pinfunction "2_2") (pintype "passive"))
      (node (ref "R32") (pin "2") (pinfunction "2_2") (pintype "passive"))
      (node (ref "R33") (pin "2") (pinfunction "2_2") (pintype "passive"))
      (node (ref "UC1") (pin "33") (pinfunction "PA12/USART1_RTS/CAN_TX/TIM1_ETR/USBDP_33") (pintype "bidirectional"))
    )
    (net (code "40") (name "/VBAT") (class "Default")
      (node (ref "UC1") (pin "1") (pinfunction "VBAT_1") (pintype "power_in"))
    )
    (net (code "41") (name "/VCC") (class "Default")
      (node (ref "AMP") (pin "5") (pinfunction "VIN_5") (pintype "bidirectional"))
      (node (ref "DAC") (pin "1") (pinfunction "VDD_1") (pintype "power_in"))
      (node (ref "P1") (pin "2") (pinfunction "VIN_2") (pintype "bidirectional"))
      (node (ref "R22") (pin "2") (pinfunction "2_2") (pintype "passive"))
      (node (ref "R26") (pin "1") (pinfunction "1_1") (pintype "passive"))
      (node (ref "R27") (pin "1") (pinfunction "1_1") (pintype "passive"))
      (node (ref "U$2") (pin "2") (pinfunction "VOUT_2") (pintype "output"))
      (node (ref "U$9") (pin "+") (pinfunction "+_+") (pintype "passive"))
    )
    (net (code "42") (name "/VIN") (class "Default")
      (node (ref "BTN") (pin "2") (pinfunction "2_2") (pintype "passive"))
      (node (ref "D3") (pin "2") (pinfunction "A_2") (pintype "passive"))
      (node (ref "R10") (pin "2") (pinfunction "2_2") (pintype "passive"))
      (node (ref "R11") (pin "2") (pinfunction "2_2") (pintype "passive"))
      (node (ref "R12") (pin "2") (pinfunction "2_2") (pintype "passive"))
      (node (ref "R13") (pin "1") (pinfunction "1_1") (pintype "passive"))
      (node (ref "R14") (pin "1") (pinfunction "1_1") (pintype "passive"))
      (node (ref "R15") (pin "1") (pinfunction "1_1") (pintype "passive"))
      (node (ref "R16") (pin "1") (pinfunction "1_1") (pintype "passive"))
      (node (ref "R17") (pin "1") (pinfunction "1_1") (pintype "passive"))
      (node (ref "R18") (pin "1") (pinfunction "1_1") (pintype "passive"))
      (node (ref "R3") (pin "1") (pinfunction "1_1") (pintype "passive"))
      (node (ref "R4") (pin "1") (pinfunction "1_1") (pintype "passive"))
      (node (ref "R5") (pin "1") (pinfunction "1_1") (pintype "passive"))
      (node (ref "R6") (pin "2") (pinfunction "2_2") (pintype "passive"))
      (node (ref "R7") (pin "2") (pinfunction "2_2") (pintype "passive"))
      (node (ref "R8") (pin "2") (pinfunction "2_2") (pintype "passive"))
      (node (ref "R9") (pin "2") (pinfunction "2_2") (pintype "passive"))
      (node (ref "U$1") (pin "4") (pinfunction "VIN_4") (pintype "bidirectional"))
      (node (ref "U$14") (pin "+") (pinfunction "+_+") (pintype "passive"))
    )
    (net (code "43") (name "/VIN_BAT") (class "Default")
      (node (ref "BTN") (pin "1") (pinfunction "1_1") (pintype "passive"))
      (node (ref "C3") (pin "2") (pinfunction "2_2") (pintype "passive"))
      (node (ref "IC1") (pin "5") (pinfunction "BAT_5") (pintype "bidirectional"))
      (node (ref "PWR") (pin "1") (pinfunction "1_1") (pintype "passive"))
    )
    (net (code "44") (name "AV+") (class "Default")
      (node (ref "C5") (pin "1") (pinfunction "1_1") (pintype "passive"))
      (node (ref "C9") (pin "1") (pinfunction "1_1") (pintype "passive"))
      (node (ref "IC3") (pin "2") (pinfunction "VOUT_2") (pintype "bidirectional"))
      (node (ref "UC1") (pin "9") (pinfunction "VDD_A_9") (pintype "power_in"))
    )
    (net (code "45") (name "AV-") (class "Default")
      (node (ref "L1") (pin "1") (pinfunction "1_1") (pintype "passive"))
    )
    (net (code "46") (name "GND") (class "Default")
      (node (ref "AMP") (pin "3") (pinfunction "GND_3") (pintype "bidirectional"))
      (node (ref "AMP") (pin "7") (pinfunction "GND_7") (pintype "bidirectional"))
      (node (ref "C10") (pin "1") (pinfunction "1_1") (pintype "passive"))
      (node (ref "C11") (pin "1") (pinfunction "1_1") (pintype "passive"))
      (node (ref "C12") (pin "2") (pinfunction "2_2") (pintype "passive"))
      (node (ref "C13") (pin "2") (pinfunction "2_2") (pintype "passive"))
      (node (ref "C14") (pin "C") (pinfunction "-_C") (pintype "passive"))
      (node (ref "C16") (pin "1") (pinfunction "1_1") (pintype "passive"))
      (node (ref "C2") (pin "1") (pinfunction "1_1") (pintype "passive"))
      (node (ref "C3") (pin "1") (pinfunction "1_1") (pintype "passive"))
      (node (ref "C4") (pin "2") (pinfunction "2_2") (pintype "passive"))
      (node (ref "C5") (pin "2") (pinfunction "2_2") (pintype "passive"))
      (node (ref "C6") (pin "2") (pinfunction "2_2") (pintype "passive"))
      (node (ref "C7") (pin "2") (pinfunction "2_2") (pintype "passive"))
      (node (ref "C8") (pin "2") (pinfunction "2_2") (pintype "passive"))
      (node (ref "C9") (pin "2") (pinfunction "2_2") (pintype "passive"))
      (node (ref "D1") (pin "C") (pinfunction "C_C") (pintype "passive"))
      (node (ref "DAC") (pin "7") (pinfunction "AVSS_7") (pintype "power_in"))
      (node (ref "IC1") (pin "1") (pinfunction "TEMP_1") (pintype "bidirectional"))
      (node (ref "IC1") (pin "3") (pinfunction "GND_3") (pintype "bidirectional"))
      (node (ref "IC2") (pin "1") (pinfunction "GND_1") (pintype "bidirectional"))
      (node (ref "IC3") (pin "1") (pinfunction "GND_1") (pintype "bidirectional"))
      (node (ref "JACK") (pin "1") (pinfunction "GND_1") (pintype "bidirectional"))
      (node (ref "L1") (pin "2") (pinfunction "2_2") (pintype "passive"))
      (node (ref "OS1") (pin "E") (pinfunction "EMITTER_E") (pintype "passive"))
      (node (ref "OS2") (pin "E") (pinfunction "EMITTER_E") (pintype "passive"))
      (node (ref "OS3") (pin "E") (pinfunction "EMITTER_E") (pintype "passive"))
      (node (ref "OS4") (pin "E") (pinfunction "EMITTER_E") (pintype "passive"))
      (node (ref "OS5") (pin "E") (pinfunction "EMITTER_E") (pintype "passive"))
      (node (ref "OS6") (pin "E") (pinfunction "EMITTER_E") (pintype "passive"))
      (node (ref "OS7") (pin "E") (pinfunction "EMITTER_E") (pintype "passive"))
      (node (ref "OS8") (pin "E") (pinfunction "EMITTER_E") (pintype "passive"))
      (node (ref "P1") (pin "3") (pinfunction "GND_3") (pintype "bidirectional"))
      (node (ref "PROGRAM") (pin "1") (pinfunction "1_1") (pintype "passive"))
      (node (ref "PWR") (pin "2") (pinfunction "2_2") (pintype "passive"))
      (node (ref "R21") (pin "1") (pinfunction "1_1") (pintype "passive"))
      (node (ref "R23") (pin "2") (pinfunction "2_2") (pintype "passive"))
      (node (ref "R24") (pin "1") (pinfunction "1_1") (pintype "passive"))
      (node (ref "R34") (pin "2") (pinfunction "2_2") (pintype "passive"))
      (node (ref "R39") (pin "2") (pinfunction "2_2") (pintype "passive"))
      (node (ref "R41") (pin "2") (pinfunction "2_2") (pintype "passive"))
      (node (ref "U$1") (pin "1") (pinfunction "GND_1") (pintype "bidirectional"))
      (node (ref "U$14") (pin "-") (pinfunction "-_-") (pintype "passive"))
      (node (ref "U$18") (pin "A1") (pinfunction "P$1_A1") (pintype "bidirectional"))
      (node (ref "U$18") (pin "A2") (pinfunction "P$1_A2") (pintype "bidirectional"))
      (node (ref "U$19") (pin "A1") (pinfunction "P$1_A1") (pintype "bidirectional"))
      (node (ref "U$19") (pin "A2") (pinfunction "P$1_A2") (pintype "bidirectional"))
      (node (ref "U$2") (pin "1") (pinfunction "GND_1") (pintype "passive"))
      (node (ref "U$20") (pin "A1") (pinfunction "P$1_A1") (pintype "bidirectional"))
      (node (ref "U$20") (pin "A2") (pinfunction "P$1_A2") (pintype "bidirectional"))
      (node (ref "U$21") (pin "A1") (pinfunction "P$1_A1") (pintype "bidirectional"))
      (node (ref "U$21") (pin "A2") (pinfunction "P$1_A2") (pintype "bidirectional"))
      (node (ref "U$22") (pin "A1") (pinfunction "P$1_A1") (pintype "bidirectional"))
      (node (ref "U$22") (pin "A2") (pinfunction "P$1_A2") (pintype "bidirectional"))
      (node (ref "U$23") (pin "A1") (pinfunction "P$1_A1") (pintype "bidirectional"))
      (node (ref "U$23") (pin "A2") (pinfunction "P$1_A2") (pintype "bidirectional"))
      (node (ref "U$24") (pin "GND") (pinfunction "GND_GND") (pintype "bidirectional"))
      (node (ref "U$28") (pin "2") (pinfunction "E_2") (pintype "passive"))
      (node (ref "U$29") (pin "2") (pinfunction "E_2") (pintype "passive"))
      (node (ref "U$31") (pin "2") (pinfunction "E_2") (pintype "passive"))
      (node (ref "U$9") (pin "-") (pinfunction "-_-") (pintype "passive"))
      (node (ref "UC1") (pin "23") (pinfunction "VSS_1_23") (pintype "power_in"))
      (node (ref "UC1") (pin "35") (pinfunction "VSS_2_35") (pintype "power_in"))
      (node (ref "UC1") (pin "47") (pinfunction "VSS_3_47") (pintype "power_in"))
      (node (ref "UC1") (pin "8") (pinfunction "VSS_A_8") (pintype "power_in"))
      (node (ref "X1") (pin "GND") (pinfunction "GND_GND") (pintype "bidirectional"))
    )
    (net (code "47") (name "Net-(AMP-INPUT)") (class "Default")
      (node (ref "AMP") (pin "2") (pinfunction "INPUT_2") (pintype "bidirectional"))
      (node (ref "R20") (pin "2") (pinfunction "2_2") (pintype "passive"))
      (node (ref "R21") (pin "2") (pinfunction "2_2") (pintype "passive"))
    )
    (net (code "48") (name "Net-(AMP-MUTE)") (class "Default")
      (node (ref "AMP") (pin "4") (pinfunction "MUTE_4") (pintype "bidirectional"))
      (node (ref "R23") (pin "1") (pinfunction "1_1") (pintype "passive"))
    )
    (net (code "49") (name "Net-(AMP-OUT+)") (class "Default")
      (node (ref "AMP") (pin "6") (pinfunction "OUT+_6") (pintype "bidirectional"))
      (node (ref "SPEAKER") (pin "1") (pinfunction "1_1") (pintype "passive"))
    )
    (net (code "50") (name "Net-(AMP-OUT-)") (class "Default")
      (node (ref "AMP") (pin "8") (pinfunction "OUT-_8") (pintype "bidirectional"))
      (node (ref "SPEAKER") (pin "2") (pinfunction "2_2") (pintype "passive"))
    )
    (net (code "51") (name "Net-(AMP-SDBY)") (class "Default")
      (node (ref "AMP") (pin "1") (pinfunction "SDBY_1") (pintype "bidirectional"))
      (node (ref "R22") (pin "1") (pinfunction "1_1") (pintype "passive"))
    )
    (net (code "52") (name "Net-(BUT-1)") (class "Default")
      (node (ref "BUT") (pin "P$1") (pinfunction "1_P$1") (pintype "passive"))
      (node (ref "BUT") (pin "P$3") (pinfunction "3_P$3") (pintype "passive"))
      (node (ref "R38") (pin "2") (pinfunction "2_2") (pintype "passive"))
    )
    (net (code "53") (name "Net-(BUT-2)") (class "Default")
      (node (ref "BUT") (pin "P$2") (pinfunction "2_P$2") (pintype "passive"))
      (node (ref "BUT") (pin "P$4") (pinfunction "4_P$4") (pintype "passive"))
      (node (ref "R39") (pin "1") (pinfunction "1_1") (pintype "passive"))
      (node (ref "UC1") (pin "37") (pinfunction "PA14/JTCK/SWCLK_37") (pintype "bidirectional"))
      (node (ref "UC1") (pin "44") (pinfunction "BOOT0_44") (pintype "input"))
    )
    (net (code "54") (name "Net-(C1-Pad2)") (class "Default")
      (node (ref "C1") (pin "2") (pinfunction "2_2") (pintype "passive"))
      (node (ref "R20") (pin "1") (pinfunction "1_1") (pintype "passive"))
    )
    (net (code "55") (name "Net-(C14-+)") (class "Default")
      (node (ref "C14") (pin "A") (pinfunction "+_A") (pintype "passive"))
      (node (ref "D2") (pin "1") (pinfunction "C_1") (pintype "passive"))
      (node (ref "D3") (pin "1") (pinfunction "C_1") (pintype "passive"))
      (node (ref "IC2") (pin "3") (pinfunction "VIN_3") (pintype "bidirectional"))
      (node (ref "IC3") (pin "3") (pinfunction "VIN_3") (pintype "bidirectional"))
    )
    (net (code "56") (name "Net-(D1-PadA)") (class "Default")
      (node (ref "D1") (pin "A") (pinfunction "A_A") (pintype "passive"))
      (node (ref "R30") (pin "2") (pinfunction "2_2") (pintype "passive"))
    )
    (net (code "57") (name "Net-(D4-PadA)") (class "Default")
      (node (ref "D4") (pin "A") (pinfunction "A_A") (pintype "passive"))
      (node (ref "R26") (pin "2") (pinfunction "2_2") (pintype "passive"))
    )
    (net (code "58") (name "Net-(D5-PadA)") (class "Default")
      (node (ref "D5") (pin "A") (pinfunction "A_A") (pintype "passive"))
      (node (ref "R27") (pin "2") (pinfunction "2_2") (pintype "passive"))
    )
    (net (code "59") (name "Net-(IC1-CHRG)") (class "Default")
      (node (ref "D4") (pin "C") (pinfunction "C_C") (pintype "passive"))
      (node (ref "IC1") (pin "7") (pinfunction "CHRG_7") (pintype "bidirectional"))
    )
    (net (code "60") (name "Net-(IC1-PROG)") (class "Default")
      (node (ref "IC1") (pin "2") (pinfunction "PROG_2") (pintype "bidirectional"))
      (node (ref "R24") (pin "2") (pinfunction "2_2") (pintype "passive"))
    )
    (net (code "61") (name "Net-(IC1-STDBY)") (class "Default")
      (node (ref "D5") (pin "C") (pinfunction "C_C") (pintype "passive"))
      (node (ref "IC1") (pin "6") (pinfunction "STDBY_6") (pintype "bidirectional"))
    )
    (net (code "62") (name "Net-(IC1-VCC)") (class "Default")
      (node (ref "C2") (pin "2") (pinfunction "2_2") (pintype "passive"))
      (node (ref "IC1") (pin "4") (pinfunction "VCC_4") (pintype "bidirectional"))
      (node (ref "R29") (pin "2") (pinfunction "2_2") (pintype "passive"))
    )
    (net (code "63") (name "Net-(JACK-IN_A)") (class "Default")
      (node (ref "JACK") (pin "2") (pinfunction "IN_A_2") (pintype "bidirectional"))
      (node (ref "JACK") (pin "5") (pinfunction "IN_B_5") (pintype "bidirectional"))
      (node (ref "R19") (pin "2") (pinfunction "2_2") (pintype "passive"))
    )
    (net (code "64") (name "Net-(JACK-OUT_A)") (class "Default")
      (node (ref "C1") (pin "1") (pinfunction "1_1") (pintype "passive"))
      (node (ref "JACK") (pin "3") (pinfunction "OUT_A_3") (pintype "bidirectional"))
      (node (ref "JACK") (pin "4") (pinfunction "OUT_B_4") (pintype "bidirectional"))
    )
    (net (code "65") (name "Net-(OS1-ANODE)") (class "Default")
      (node (ref "OS1") (pin "A") (pinfunction "ANODE_A") (pintype "passive"))
      (node (ref "R3") (pin "2") (pinfunction "2_2") (pintype "passive"))
    )
    (net (code "66") (name "Net-(OS2-ANODE)") (class "Default")
      (node (ref "OS2") (pin "A") (pinfunction "ANODE_A") (pintype "passive"))
      (node (ref "R7") (pin "1") (pinfunction "1_1") (pintype "passive"))
    )
    (net (code "67") (name "Net-(OS3-ANODE)") (class "Default")
      (node (ref "OS3") (pin "A") (pinfunction "ANODE_A") (pintype "passive"))
      (node (ref "R10") (pin "1") (pinfunction "1_1") (pintype "passive"))
    )
    (net (code "68") (name "Net-(OS4-ANODE)") (class "Default")
      (node (ref "OS4") (pin "A") (pinfunction "ANODE_A") (pintype "passive"))
      (node (ref "R11") (pin "1") (pinfunction "1_1") (pintype "passive"))
    )
    (net (code "69") (name "Net-(OS5-ANODE)") (class "Default")
      (node (ref "OS5") (pin "A") (pinfunction "ANODE_A") (pintype "passive"))
      (node (ref "R5") (pin "2") (pinfunction "2_2") (pintype "passive"))
    )
    (net (code "70") (name "Net-(OS6-ANODE)") (class "Default")
      (node (ref "OS6") (pin "A") (pinfunction "ANODE_A") (pintype "passive"))
      (node (ref "R8") (pin "1") (pinfunction "1_1") (pintype "passive"))
    )
    (net (code "71") (name "Net-(OS7-ANODE)") (class "Default")
      (node (ref "OS7") (pin "A") (pinfunction "ANODE_A") (pintype "passive"))
      (node (ref "R9") (pin "1") (pinfunction "1_1") (pintype "passive"))
    )
    (net (code "72") (name "Net-(OS8-ANODE)") (class "Default")
      (node (ref "OS8") (pin "A") (pinfunction "ANODE_A") (pintype "passive"))
      (node (ref "R12") (pin "1") (pinfunction "1_1") (pintype "passive"))
    )
    (net (code "73") (name "Net-(R31-Pad1)") (class "Default")
      (node (ref "R31") (pin "1") (pinfunction "1_1") (pintype "passive"))
      (node (ref "X1") (pin "D-") (pinfunction "D-_D-") (pintype "bidirectional"))
    )
    (net (code "74") (name "Net-(R32-Pad1)") (class "Default")
      (node (ref "R32") (pin "1") (pinfunction "1_1") (pintype "passive"))
      (node (ref "X1") (pin "D+") (pinfunction "D+_D+") (pintype "bidirectional"))
    )
    (net (code "75") (name "Net-(RESET-1)") (class "Default")
      (node (ref "R41") (pin "1") (pinfunction "1_1") (pintype "passive"))
      (node (ref "RESET") (pin "P$1") (pinfunction "1_P$1") (pintype "passive"))
      (node (ref "RESET") (pin "P$3") (pinfunction "3_P$3") (pintype "passive"))
    )
    (net (code "76") (name "Net-(U$1-C+)") (class "Default")
      (node (ref "C15") (pin "2") (pinfunction "2_2") (pintype "passive"))
      (node (ref "U$1") (pin "5") (pinfunction "C+_5") (pintype "bidirectional"))
    )
    (net (code "77") (name "Net-(U$1-C-)") (class "Default")
      (node (ref "C15") (pin "1") (pinfunction "1_1") (pintype "passive"))
      (node (ref "U$1") (pin "3") (pinfunction "C-_3") (pintype "bidirectional"))
    )
    (net (code "78") (name "Net-(U$1-VOUT)") (class "Default")
      (node (ref "C16") (pin "2") (pinfunction "2_2") (pintype "passive"))
      (node (ref "U$1") (pin "2") (pinfunction "VOUT_2") (pintype "bidirectional"))
      (node (ref "U$2") (pin "3") (pinfunction "VIN_3") (pintype "input"))
    )
    (net (code "79") (name "Net-(U$17-B)") (class "Default")
      (node (ref "R34") (pin "1") (pinfunction "1_1") (pintype "passive"))
      (node (ref "R35") (pin "2") (pinfunction "2_2") (pintype "passive"))
      (node (ref "U$17") (pin "1") (pinfunction "B_1") (pintype "passive"))
      (node (ref "U$31") (pin "3") (pinfunction "C_3") (pintype "passive"))
    )
    (net (code "80") (name "Net-(U$17-E)") (class "Default")
      (node (ref "R33") (pin "1") (pinfunction "1_1") (pintype "passive"))
      (node (ref "U$17") (pin "2") (pinfunction "E_2") (pintype "passive"))
    )
    (net (code "81") (name "Net-(U$28-B)") (class "Default")
      (node (ref "R1") (pin "2") (pinfunction "2_2") (pintype "passive"))
      (node (ref "U$28") (pin "1") (pinfunction "B_1") (pintype "passive"))
    )
    (net (code "82") (name "Net-(U$29-B)") (class "Default")
      (node (ref "R2") (pin "2") (pinfunction "2_2") (pintype "passive"))
      (node (ref "U$29") (pin "1") (pinfunction "B_1") (pintype "passive"))
    )
    (net (code "83") (name "Net-(U$31-B)") (class "Default")
      (node (ref "R36") (pin "2") (pinfunction "2_2") (pintype "passive"))
      (node (ref "R37") (pin "2") (pinfunction "2_2") (pintype "passive"))
      (node (ref "U$31") (pin "1") (pinfunction "B_1") (pintype "passive"))
    )
    (net (code "84") (name "Net-(UC1-PA13{slash}JTMS{slash}SWDIO)") (class "Default")
      (node (ref "R30") (pin "1") (pinfunction "1_1") (pintype "passive"))
      (node (ref "UC1") (pin "34") (pinfunction "PA13/JTMS/SWDIO_34") (pintype "bidirectional"))
    )
    (net (code "85") (name "unconnected-(DAC-~{SHDN}-Pad6)") (class "Default")
      (node (ref "DAC") (pin "6") (pinfunction "~{SHDN}_6") (pintype "input"))
    )
    (net (code "86") (name "unconnected-(UC1-PB1{slash}ADC12_IN9{slash}TIM3_CH4-Pad19)") (class "Default")
      (node (ref "UC1") (pin "19") (pinfunction "PB1/ADC12_IN9/TIM3_CH4_19") (pintype "bidirectional"))
    )
    (net (code "87") (name "unconnected-(UC1-PB14{slash}SPI2_MISO{slash}USART3_RTS{slash}TIM1_CH2N-Pad27)") (class "Default")
      (node (ref "UC1") (pin "27") (pinfunction "PB14/SPI2_MISO/USART3_RTS/TIM1_CH2N_27") (pintype "input"))
    )
    (net (code "88") (name "unconnected-(UC1-PC13-TAMPER-RTC-Pad2)") (class "Default")
      (node (ref "UC1") (pin "2") (pinfunction "PC13-TAMPER-RTC_2") (pintype "input"))
    )
  )
)
